# Potentiometer.net
KiCad netlist of a schematic drawn in Altium Designer
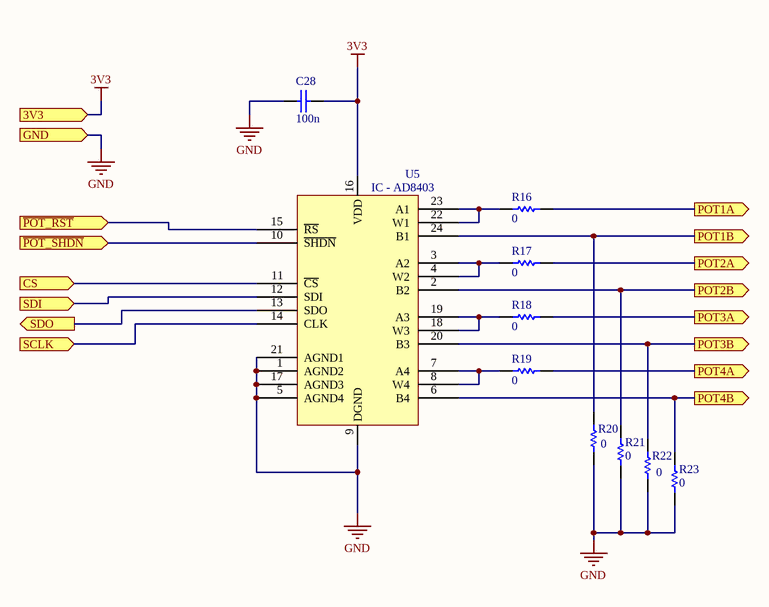
[diagram p0: Potentiometer.SchDoc]

(export (version "E")
  (design (tool "Eeschema 10.0.6"))
  (components
    (comp (ref "C28")
      (value "100n")
      (footprint "CS-0603")
      (fields
        (field (name "TOLERANCE") "10%")
        (field (name "VOLTAGE") "16V")
        (field (name "Comment") "CS - CAPACITOR")
      )
      (libsource (lib "CHINOOK_LIBRARY") (part "CS - CAPACITOR"))
    )
    (comp (ref "R16")
      (value "0")
      (footprint "RS-0603")
      (fields
        (field (name "TOLERANCE") "RES TOL")
        (field (name "POWER") "RES POWER")
        (field (name "Comment") "RS - RESISTOR")
      )
      (libsource (lib "CHINOOK_LIBRARY") (part "RS - RESISTOR"))
    )
    (comp (ref "R17")
      (value "0")
      (footprint "RS-0603")
      (fields
        (field (name "TOLERANCE") "RES TOL")
        (field (name "POWER") "RES POWER")
        (field (name "Comment") "RS - RESISTOR")
      )
      (libsource (lib "CHINOOK_LIBRARY") (part "RS - RESISTOR"))
    )
    (comp (ref "R18")
      (value "0")
      (footprint "RS-0603")
      (fields
        (field (name "TOLERANCE") "RES TOL")
        (field (name "POWER") "RES POWER")
        (field (name "Comment") "RS - RESISTOR")
      )
      (libsource (lib "CHINOOK_LIBRARY") (part "RS - RESISTOR"))
    )
    (comp (ref "R19")
      (value "0")
      (footprint "RS-0603")
      (fields
        (field (name "TOLERANCE") "RES TOL")
        (field (name "POWER") "RES POWER")
        (field (name "Comment") "RS - RESISTOR")
      )
      (libsource (lib "CHINOOK_LIBRARY") (part "RS - RESISTOR"))
    )
    (comp (ref "R20")
      (value "0")
      (footprint "RS-0603")
      (fields
        (field (name "TOLERANCE") "RES TOL")
        (field (name "POWER") "RES POWER")
        (field (name "Comment") "RS - RESISTOR")
      )
      (libsource (lib "CHINOOK_LIBRARY") (part "RS - RESISTOR"))
    )
    (comp (ref "R21")
      (value "0")
      (footprint "RS-0603")
      (fields
        (field (name "TOLERANCE") "RES TOL")
        (field (name "POWER") "RES POWER")
        (field (name "Comment") "RS - RESISTOR")
      )
      (libsource (lib "CHINOOK_LIBRARY") (part "RS - RESISTOR"))
    )
    (comp (ref "R22")
      (value "0")
      (footprint "RS-0603")
      (fields
        (field (name "TOLERANCE") "RES TOL")
        (field (name "POWER") "RES POWER")
        (field (name "Comment") "RS - RESISTOR")
      )
      (libsource (lib "CHINOOK_LIBRARY") (part "RS - RESISTOR"))
    )
    (comp (ref "R23")
      (value "0")
      (footprint "RS-0603")
      (fields
        (field (name "TOLERANCE") "RES TOL")
        (field (name "POWER") "RES POWER")
        (field (name "Comment") "RS - RESISTOR")
      )
      (libsource (lib "CHINOOK_LIBRARY") (part "RS - RESISTOR"))
    )
    (comp (ref "U5")
      (value "IC - AD8403")
      (footprint "IC-SOIC-24")
      (description "DIGITAL POTENTIOMETER")
      (libsource (lib "CHINOOK_LIBRARY") (part "IC - AD8403"))
    )
  )
  (nets
    (net (code "1") (name "/CS") (class "Default")
      (node (ref "U5") (pin "11") (pinfunction "~{CS}_11") (pintype "passive"))
    )
    (net (code "2") (name "/POT1A") (class "Default")
      (node (ref "R16") (pin "1") (pinfunction "1_1") (pintype "passive"))
    )
    (net (code "3") (name "/POT1B") (class "Default")
      (node (ref "R20") (pin "1") (pinfunction "1_1") (pintype "passive"))
      (node (ref "U5") (pin "24") (pinfunction "B1_24") (pintype "passive"))
    )
    (net (code "4") (name "/POT2A") (class "Default")
      (node (ref "R17") (pin "1") (pinfunction "1_1") (pintype "passive"))
    )
    (net (code "5") (name "/POT2B") (class "Default")
      (node (ref "R21") (pin "1") (pinfunction "1_1") (pintype "passive"))
      (node (ref "U5") (pin "2") (pinfunction "B2_2") (pintype "passive"))
    )
    (net (code "6") (name "/POT3A") (class "Default")
      (node (ref "R18") (pin "1") (pinfunction "1_1") (pintype "passive"))
    )
    (net (code "7") (name "/POT3B") (class "Default")
      (node (ref "R22") (pin "1") (pinfunction "1_1") (pintype "passive"))
      (node (ref "U5") (pin "20") (pinfunction "B3_20") (pintype "passive"))
    )
    (net (code "8") (name "/POT4A") (class "Default")
      (node (ref "R19") (pin "1") (pinfunction "1_1") (pintype "passive"))
    )
    (net (code "9") (name "/POT4B") (class "Default")
      (node (ref "R23") (pin "1") (pinfunction "1_1") (pintype "passive"))
      (node (ref "U5") (pin "6") (pinfunction "B4_6") (pintype "passive"))
    )
    (net (code "10") (name "/SCLK") (class "Default")
      (node (ref "U5") (pin "14") (pinfunction "CLK_14") (pintype "passive"))
    )
    (net (code "11") (name "/SDI") (class "Default")
      (node (ref "U5") (pin "12") (pinfunction "SDI_12") (pintype "passive"))
    )
    (net (code "12") (name "/SDO") (class "Default")
      (node (ref "U5") (pin "13") (pinfunction "SDO_13") (pintype "passive"))
    )
    (net (code "13") (name "/~{POT_RST}") (class "Default")
      (node (ref "U5") (pin "15") (pinfunction "~{RS}_15") (pintype "passive"))
    )
    (net (code "14") (name "/~{POT_SHDN}") (class "Default")
      (node (ref "U5") (pin "10") (pinfunction "~{SHDN}_10") (pintype "passive"))
    )
    (net (code "15") (name "3V3") (class "Default")
      (node (ref "C28") (pin "1") (pinfunction "1_1") (pintype "passive"))
      (node (ref "U5") (pin "16") (pinfunction "VDD_16") (pintype "passive"))
    )
    (net (code "16") (name "GND") (class "Default")
      (node (ref "C28") (pin "2") (pinfunction "2_2") (pintype "passive"))
      (node (ref "R20") (pin "2") (pinfunction "2_2") (pintype "passive"))
      (node (ref "R21") (pin "2") (pinfunction "2_2") (pintype "passive"))
      (node (ref "R22") (pin "2") (pinfunction "2_2") (pintype "passive"))
      (node (ref "R23") (pin "2") (pinfunction "2_2") (pintype "passive"))
      (node (ref "U5") (pin "1") (pinfunction "AGND2_1") (pintype "passive"))
      (node (ref "U5") (pin "17") (pinfunction "AGND3_17") (pintype "passive"))
      (node (ref "U5") (pin "21") (pinfunction "AGND1_21") (pintype "passive"))
      (node (ref "U5") (pin "5") (pinfunction "AGND4_5") (pintype "passive"))
      (node (ref "U5") (pin "9") (pinfunction "DGND_9") (pintype "passive"))
    )
    (net (code "17") (name "Net-(U5-A1)") (class "Default")
      (node (ref "R16") (pin "2") (pinfunction "2_2") (pintype "passive"))
      (node (ref "U5") (pin "22") (pinfunction "W1_22") (pintype "passive"))
      (node (ref "U5") (pin "23") (pinfunction "A1_23") (pintype "passive"))
    )
    (net (code "18") (name "Net-(U5-A2)") (class "Default")
      (node (ref "R17") (pin "2") (pinfunction "2_2") (pintype "passive"))
      (node (ref "U5") (pin "3") (pinfunction "A2_3") (pintype "passive"))
      (node (ref "U5") (pin "4") (pinfunction "W2_4") (pintype "passive"))
    )
    (net (code "19") (name "Net-(U5-A3)") (class "Default")
      (node (ref "R18") (pin "2") (pinfunction "2_2") (pintype "passive"))
      (node (ref "U5") (pin "18") (pinfunction "W3_18") (pintype "passive"))
      (node (ref "U5") (pin "19") (pinfunction "A3_19") (pintype "passive"))
    )
    (net (code "20") (name "Net-(U5-A4)") (class "Default")
      (node (ref "R19") (pin "2") (pinfunction "2_2") (pintype "passive"))
      (node (ref "U5") (pin "7") (pinfunction "A4_7") (pintype "passive"))
      (node (ref "U5") (pin "8") (pinfunction "W4_8") (pintype "passive"))
    )
  )
)
